# esquemaProyecto.net
KiCad netlist of a schematic drawn in EAGLE
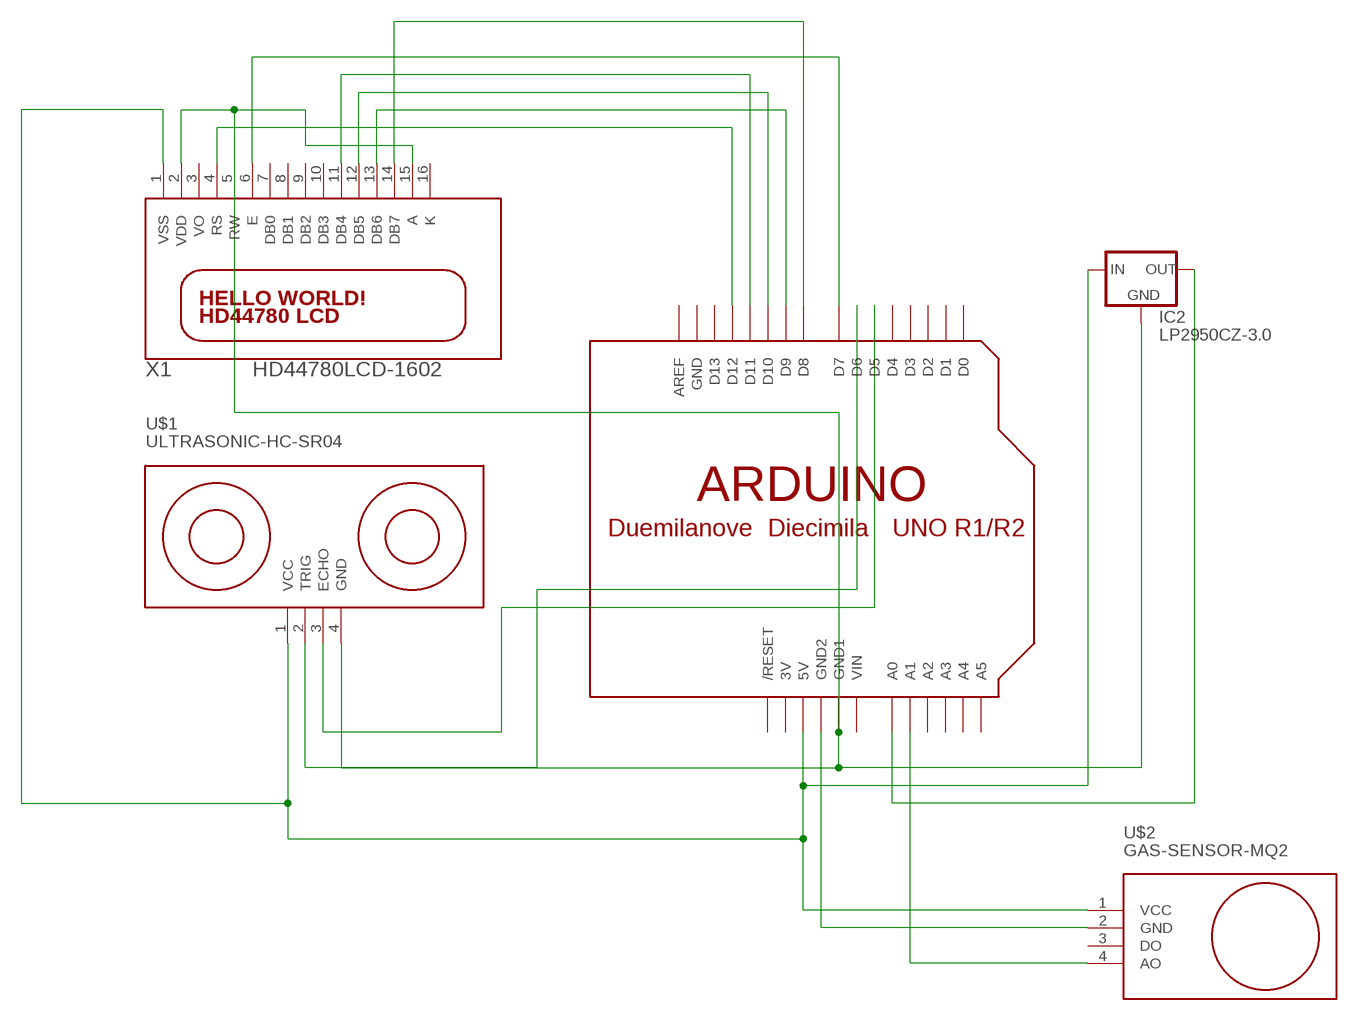
[diagram p0: schematic, sheet 1]

(export (version "E")
  (design (tool "Eeschema 10.0.6"))
  (components
    (comp (ref "IC2")
      (value "LP2950CZ-3.0")
      (footprint "eagle-import:TO92")
      (libsource (lib "eagle-import") (part "LP2950?CZ-3.0"))
    )
    (comp (ref "U$1")
      (value "ULTRASONIC-HC-SR04")
      (footprint "eagle-import:ULTRASONIC-HC-SR04")
      (libsource (lib "eagle-import") (part "ULTRASONIC-HC-SR04"))
    )
    (comp (ref "U$2")
      (value "GAS-SENSOR-MQ2")
      (footprint "eagle-import:GAS-SENSOR-MQ2")
      (libsource (lib "eagle-import") (part "GAS-SENSOR-MQ2"))
    )
    (comp (ref "U$3")
      (value "ARDUINO-BPLACE")
      (footprint "eagle-import:ARDUINO-BPLACE")
      (libsource (lib "eagle-import") (part "ARDUINO-BPLACE"))
    )
    (comp (ref "X1")
      (value "HD44780LCD-1602")
      (footprint "eagle-import:LCD1602")
      (libsource (lib "eagle-import") (part "HD44780LCD-1602"))
    )
  )
  (nets
    (net (code "1") (name "/3V") (class "Default")
      (node (ref "U$3") (pin "3V") (pinfunction "3V_3V") (pintype "power_in"))
    )
    (net (code "2") (name "/GND") (class "Default")
      (node (ref "U$3") (pin "GND") (pinfunction "GND_GND") (pintype "power_in"))
    )
    (net (code "3") (name "/VIN") (class "Default")
      (node (ref "U$3") (pin "VIN") (pinfunction "VIN_VIN") (pintype "power_in"))
    )
    (net (code "4") (name "Net-(IC2-GND)") (class "Default")
      (node (ref "IC2") (pin "2") (pinfunction "GND_2") (pintype "input"))
      (node (ref "U$1") (pin "4") (pinfunction "GND_4") (pintype "power_in"))
      (node (ref "U$3") (pin "GND1") (pinfunction "GND1_GND1") (pintype "power_in"))
      (node (ref "X1") (pin "15") (pinfunction "A_15") (pintype "input"))
      (node (ref "X1") (pin "2") (pinfunction "VDD_2") (pintype "power_in"))
      (node (ref "X1") (pin "5") (pinfunction "RW_5") (pintype "input"))
    )
    (net (code "5") (name "Net-(IC2-IN)") (class "Default")
      (node (ref "IC2") (pin "3") (pinfunction "IN_3") (pintype "input"))
      (node (ref "U$1") (pin "1") (pinfunction "VCC_1") (pintype "power_in"))
      (node (ref "U$2") (pin "1") (pinfunction "VCC_1") (pintype "power_in"))
      (node (ref "U$3") (pin "5V") (pinfunction "5V_5V") (pintype "power_in"))
      (node (ref "X1") (pin "1") (pinfunction "VSS_1") (pintype "power_in"))
    )
    (net (code "6") (name "Net-(IC2-OUT)") (class "Default")
      (node (ref "IC2") (pin "1") (pinfunction "OUT_1") (pintype "passive"))
      (node (ref "U$3") (pin "A0") (pinfunction "A0_A0") (pintype "bidirectional"))
    )
    (net (code "7") (name "Net-(U$1-ECHO)") (class "Default")
      (node (ref "U$1") (pin "3") (pinfunction "ECHO_3") (pintype "output"))
      (node (ref "U$3") (pin "D5") (pinfunction "D5_D5") (pintype "bidirectional"))
    )
    (net (code "8") (name "Net-(U$1-TRIG)") (class "Default")
      (node (ref "U$1") (pin "2") (pinfunction "TRIG_2") (pintype "input"))
      (node (ref "U$3") (pin "D6") (pinfunction "D6_D6") (pintype "bidirectional"))
    )
    (net (code "9") (name "Net-(U$2-AO)") (class "Default")
      (node (ref "U$2") (pin "4") (pinfunction "AO_4") (pintype "output"))
      (node (ref "U$3") (pin "A1") (pinfunction "A1_A1") (pintype "bidirectional"))
    )
    (net (code "10") (name "Net-(U$2-GND)") (class "Default")
      (node (ref "U$2") (pin "2") (pinfunction "GND_2") (pintype "power_in"))
      (node (ref "U$3") (pin "GND2") (pinfunction "GND2_GND2") (pintype "power_in"))
    )
    (net (code "11") (name "Net-(X1-DB4)") (class "Default")
      (node (ref "U$3") (pin "D11") (pinfunction "D11_D11") (pintype "bidirectional"))
      (node (ref "X1") (pin "11") (pinfunction "DB4_11") (pintype "bidirectional"))
    )
    (net (code "12") (name "Net-(X1-DB5)") (class "Default")
      (node (ref "U$3") (pin "D10") (pinfunction "D10_D10") (pintype "bidirectional"))
      (node (ref "X1") (pin "12") (pinfunction "DB5_12") (pintype "bidirectional"))
    )
    (net (code "13") (name "Net-(X1-DB6)") (class "Default")
      (node (ref "U$3") (pin "D9") (pinfunction "D9_D9") (pintype "bidirectional"))
      (node (ref "X1") (pin "13") (pinfunction "DB6_13") (pintype "bidirectional"))
    )
    (net (code "14") (name "Net-(X1-DB7)") (class "Default")
      (node (ref "U$3") (pin "D8") (pinfunction "D8_D8") (pintype "bidirectional"))
      (node (ref "X1") (pin "14") (pinfunction "DB7_14") (pintype "bidirectional"))
    )
    (net (code "15") (name "Net-(X1-E)") (class "Default")
      (node (ref "U$3") (pin "D7") (pinfunction "D7_D7") (pintype "bidirectional"))
      (node (ref "X1") (pin "6") (pinfunction "E_6") (pintype "input"))
    )
    (net (code "16") (name "Net-(X1-RS)") (class "Default")
      (node (ref "U$3") (pin "D12") (pinfunction "D12_D12") (pintype "bidirectional"))
      (node (ref "X1") (pin "4") (pinfunction "RS_4") (pintype "input"))
    )
    (net (code "17") (name "unconnected-(U$2-DO-Pad3)") (class "Default")
      (node (ref "U$2") (pin "3") (pinfunction "DO_3") (pintype "output"))
    )
    (net (code "18") (name "unconnected-(U$3-PadA2)") (class "Default")
      (node (ref "U$3") (pin "A2") (pinfunction "A2_A2") (pintype "bidirectional"))
    )
    (net (code "19") (name "unconnected-(U$3-PadA3)") (class "Default")
      (node (ref "U$3") (pin "A3") (pinfunction "A3_A3") (pintype "bidirectional"))
    )
    (net (code "20") (name "unconnected-(U$3-PadA4)") (class "Default")
      (node (ref "U$3") (pin "A4") (pinfunction "A4_A4") (pintype "bidirectional"))
    )
    (net (code "21") (name "unconnected-(U$3-PadA5)") (class "Default")
      (node (ref "U$3") (pin "A5") (pinfunction "A5_A5") (pintype "bidirectional"))
    )
    (net (code "22") (name "unconnected-(U$3-PadAREF)") (class "Default")
      (node (ref "U$3") (pin "AREF") (pinfunction "AREF_AREF") (pintype "bidirectional"))
    )
    (net (code "23") (name "unconnected-(U$3-PadD0)") (class "Default")
      (node (ref "U$3") (pin "D0") (pinfunction "D0_D0") (pintype "bidirectional"))
    )
    (net (code "24") (name "unconnected-(U$3-PadD1)") (class "Default")
      (node (ref "U$3") (pin "D1") (pinfunction "D1_D1") (pintype "bidirectional"))
    )
    (net (code "25") (name "unconnected-(U$3-PadD2)") (class "Default")
      (node (ref "U$3") (pin "D2") (pinfunction "D2_D2") (pintype "bidirectional"))
    )
    (net (code "26") (name "unconnected-(U$3-PadD3)") (class "Default")
      (node (ref "U$3") (pin "D3") (pinfunction "D3_D3") (pintype "bidirectional"))
    )
    (net (code "27") (name "unconnected-(U$3-PadD4)") (class "Default")
      (node (ref "U$3") (pin "D4") (pinfunction "D4_D4") (pintype "bidirectional"))
    )
    (net (code "28") (name "unconnected-(U$3-PadD13)") (class "Default")
      (node (ref "U$3") (pin "D13") (pinfunction "D13_D13") (pintype "bidirectional"))
    )
    (net (code "29") (name "unconnected-(U$3-{slash}RESET-PadRESET)") (class "Default")
      (node (ref "U$3") (pin "RESET") (pinfunction "/RESET_RESET") (pintype "bidirectional"))
    )
    (net (code "30") (name "unconnected-(X1-DB0-Pad7)") (class "Default")
      (node (ref "X1") (pin "7") (pinfunction "DB0_7") (pintype "bidirectional"))
    )
    (net (code "31") (name "unconnected-(X1-DB1-Pad8)") (class "Default")
      (node (ref "X1") (pin "8") (pinfunction "DB1_8") (pintype "bidirectional"))
    )
    (net (code "32") (name "unconnected-(X1-DB2-Pad9)") (class "Default")
      (node (ref "X1") (pin "9") (pinfunction "DB2_9") (pintype "bidirectional"))
    )
    (net (code "33") (name "unconnected-(X1-DB3-Pad10)") (class "Default")
      (node (ref "X1") (pin "10") (pinfunction "DB3_10") (pintype "bidirectional"))
    )
    (net (code "34") (name "unconnected-(X1-K-Pad16)") (class "Default")
      (node (ref "X1") (pin "16") (pinfunction "K_16") (pintype "input"))
    )
    (net (code "35") (name "unconnected-(X1-VO-Pad3)") (class "Default")
      (node (ref "X1") (pin "3") (pinfunction "VO_3") (pintype "input"))
    )
  )
)
